# Sheet1.net
KiCad netlist of a schematic drawn in Altium Designer
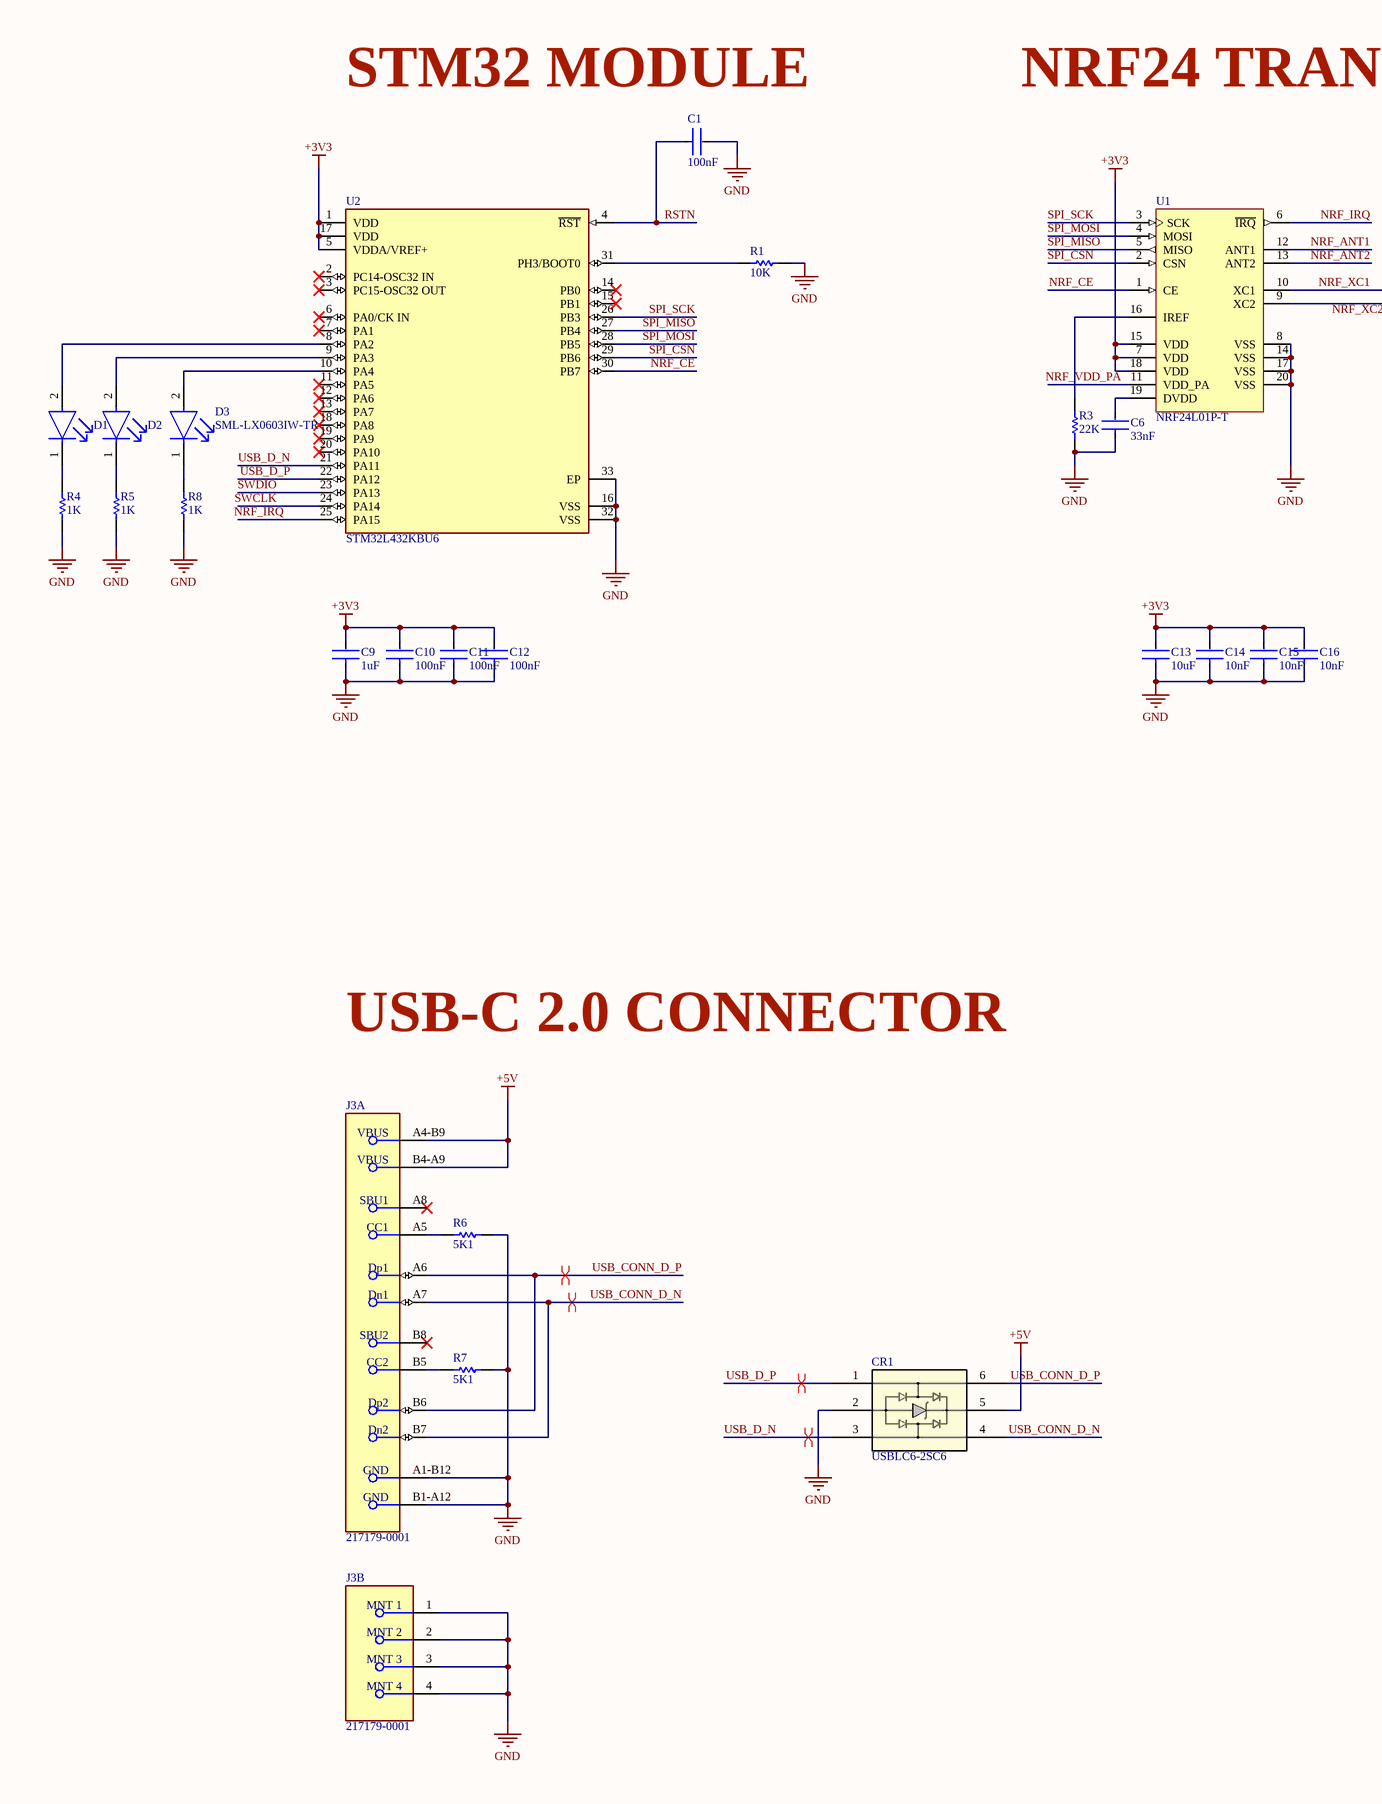
[diagram p0: Sheet1.SchDoc, left]
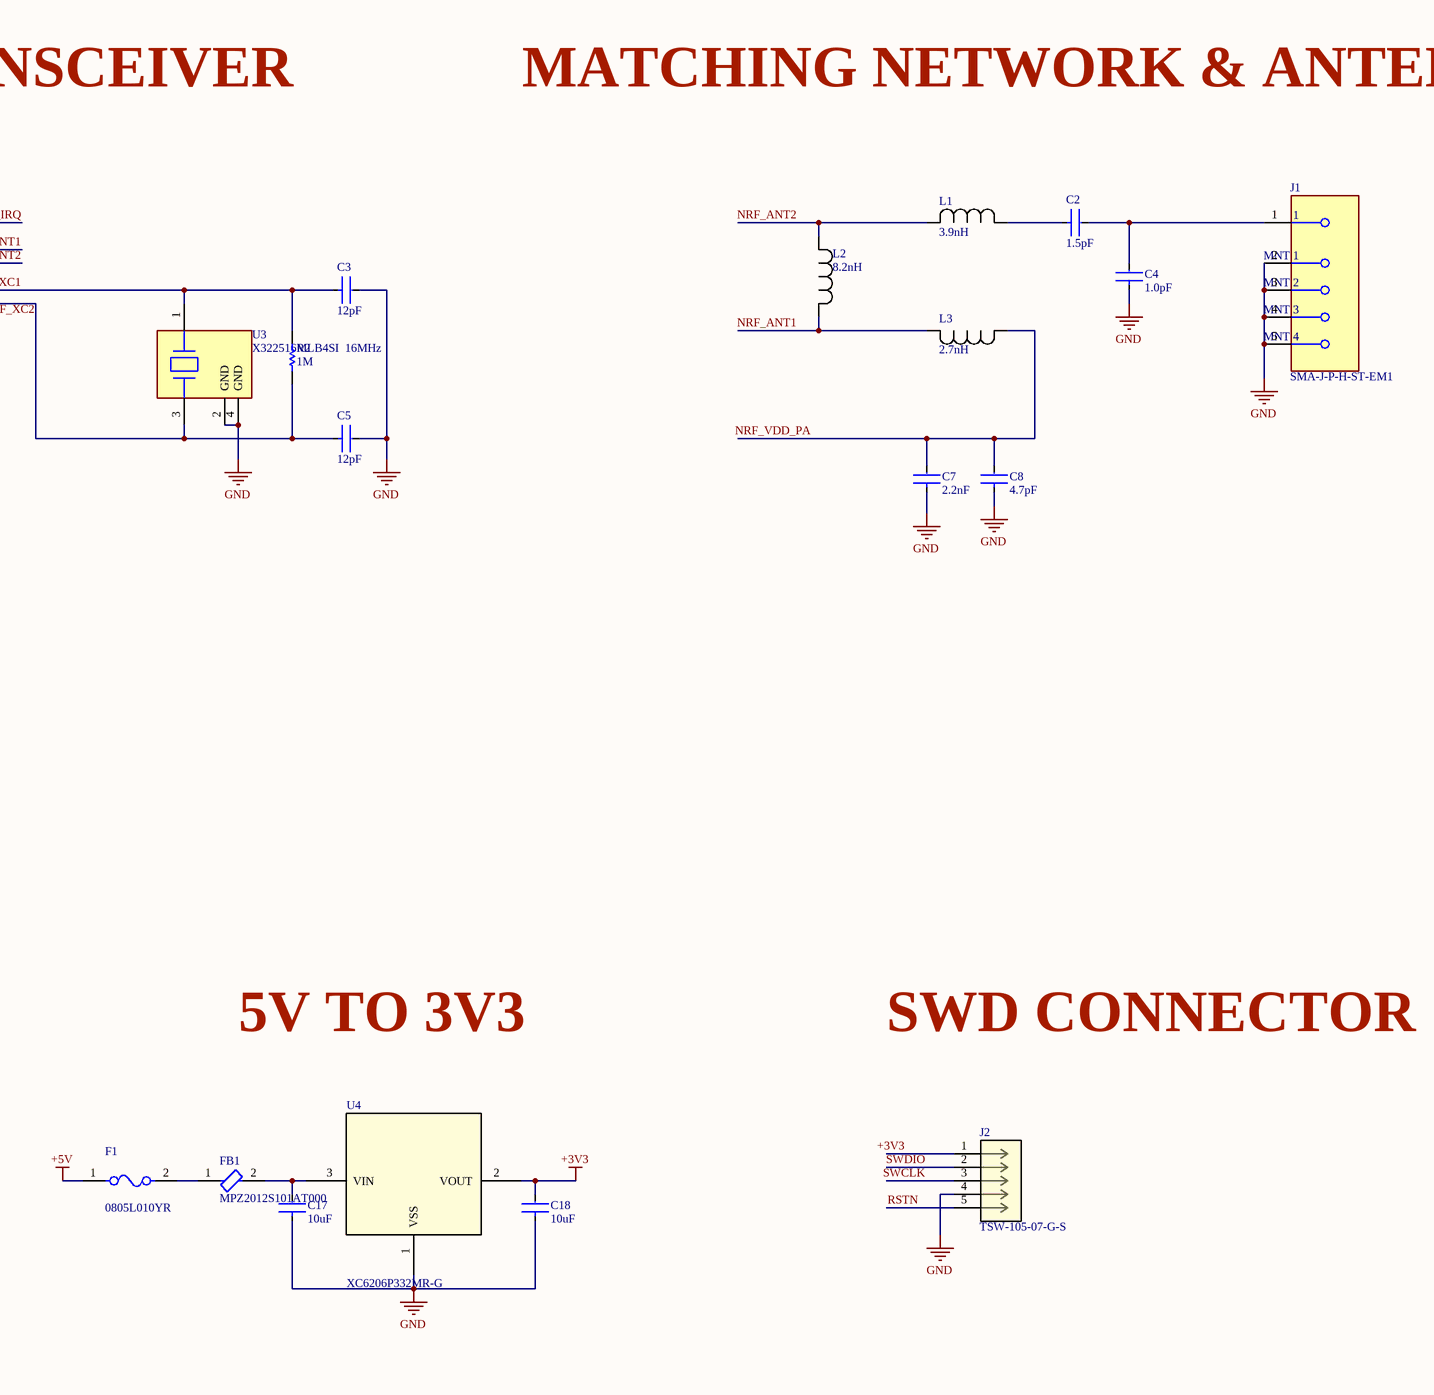
[diagram p1: Sheet1.SchDoc, right]

(export (version "E")
  (design (tool "Eeschema 10.0.6"))
  (components
    (comp (ref "C1")
      (value "100nF")
      (footprint "CAPC1005X55N")
      (description "Chip Capacitor, 100 nF")
      (fields (field (name "LCSC PART #") "C1525"))
      (libsource (lib "Schlib1") (part "CAP-0402-100NF"))
    )
    (comp (ref "C2")
      (value "1.5pF")
      (footprint "CAPC1005X55N")
      (description "Chip Capacitor, 1.5 pF")
      (fields (field (name "LCSC PART #") "C76901"))
      (libsource (lib "Schlib1") (part "CAP-0402-1P5F"))
    )
    (comp (ref "C3")
      (value "12pF")
      (footprint "CAPC1005X55N")
      (description "Chip Capacitor, 12 pF")
      (fields (field (name "LCSC PART #") "C2235030"))
      (libsource (lib "Schlib1") (part "CAP-0402-12PF"))
    )
    (comp (ref "C4")
      (value "1.0pF")
      (footprint "CAPC1005X55N")
      (description "Chip Capacitor, 1.0 pF")
      (fields (field (name "LCSC PART #") "C76898"))
      (libsource (lib "Schlib1") (part "CAP-0402-1PF"))
    )
    (comp (ref "C5")
      (value "12pF")
      (footprint "CAPC1005X55N")
      (description "Chip Capacitor, 12 pF")
      (fields (field (name "LCSC PART #") "C2235030"))
      (libsource (lib "Schlib1") (part "CAP-0402-12PF"))
    )
    (comp (ref "C6")
      (value "33nF")
      (footprint "CAPC1005X55N")
      (description "Chip Capacitor, 33 nF")
      (fields (field (name "LCSC PART #") "C126535"))
      (libsource (lib "Schlib1") (part "CAP-0402-33NF"))
    )
    (comp (ref "C7")
      (value "2.2nF")
      (footprint "CAPC1005X55N")
      (description "Chip Capacitor, 2.2 nF")
      (fields (field (name "LCSC PART #") "C2987940"))
      (libsource (lib "Schlib1") (part "CAP-0402-2N2F"))
    )
    (comp (ref "C8")
      (value "4.7pF")
      (footprint "CAPC1005X55N")
      (description "Chip Capacitor, 4.7 pF")
      (fields (field (name "LCSC PART #") "C161327"))
      (libsource (lib "Schlib1") (part "CAP-0402-4P7F"))
    )
    (comp (ref "C9")
      (value "1uF")
      (footprint "CAPC1005X55N")
      (description "Chip Capacitor, 1 uF")
      (fields (field (name "LCSC PART #") "C52923"))
      (libsource (lib "Schlib1") (part "CAP-0402-1UF"))
    )
    (comp (ref "C10")
      (value "100nF")
      (footprint "CAPC1005X55N")
      (description "Chip Capacitor, 100 nF")
      (fields (field (name "LCSC PART #") "C1525"))
      (libsource (lib "Schlib1") (part "CAP-0402-100NF"))
    )
    (comp (ref "C11")
      (value "100nF")
      (footprint "CAPC1005X55N")
      (description "Chip Capacitor, 100 nF")
      (fields (field (name "LCSC PART #") "C1525"))
      (libsource (lib "Schlib1") (part "CAP-0402-100NF"))
    )
    (comp (ref "C12")
      (value "100nF")
      (footprint "CAPC1005X55N")
      (description "Chip Capacitor, 100 nF")
      (fields (field (name "LCSC PART #") "C1525"))
      (libsource (lib "Schlib1") (part "CAP-0402-100NF"))
    )
    (comp (ref "C13")
      (value "10uF")
      (footprint "CAPC1608X90")
      (description "Chip Capacitor, 10 uF")
      (fields (field (name "LCSC PART #") "C22418930"))
      (libsource (lib "Schlib1") (part "CAP-0603-10UF"))
    )
    (comp (ref "C14")
      (value "10nF")
      (footprint "CAPC1005X55N")
      (description "Chip Capacitor, 10 nF")
      (fields (field (name "LCSC PART #") "C15195"))
      (libsource (lib "Schlib1") (part "CAP-0402-10NF"))
    )
    (comp (ref "C15")
      (value "10nF")
      (footprint "CAPC1005X55N")
      (description "Chip Capacitor, 10 nF")
      (fields (field (name "LCSC PART #") "C15195"))
      (libsource (lib "Schlib1") (part "CAP-0402-10NF"))
    )
    (comp (ref "C16")
      (value "10nF")
      (footprint "CAPC1005X55N")
      (description "Chip Capacitor, 10 nF")
      (fields (field (name "LCSC PART #") "C15195"))
      (libsource (lib "Schlib1") (part "CAP-0402-10NF"))
    )
    (comp (ref "C17")
      (value "10uF")
      (footprint "CAPC1608X90")
      (description "Chip Capacitor, 10 uF")
      (fields (field (name "LCSC PART #") "C22418930"))
      (libsource (lib "Schlib1") (part "CAP-0603-10UF"))
    )
    (comp (ref "C18")
      (value "10uF")
      (footprint "CAPC1608X90")
      (description "Chip Capacitor, 10 uF")
      (fields (field (name "LCSC PART #") "C22418930"))
      (libsource (lib "Schlib1") (part "CAP-0603-10UF"))
    )
    (comp (ref "CR1")
      (value "USBLC6-2SC6")
      (footprint "SOT23-6L_STM")
      (description "ESD Protection for USB 2.0 High Speed")
      (fields
        (field (name "LCSC PART #") "C5261088")
        (field (name "COPYRIGHT") "Copyright (C) 2025 Ultra Librarian. All rights reserved.")
      )
      (libsource (lib "Schlib1") (part "USBLC6-2SC6"))
    )
    (comp (ref "D1")
      (value "SML-LX0603IW-TR")
      (footprint "FP-SML-LX0603IW-TR-MFG")
      (description "LED RED DIFFUSED SMD")
      (fields (field (name "LCSC PART #") "C5354817"))
      (libsource (lib "Schlib1") (part "SML-LX0603IW-TR"))
    )
    (comp (ref "D2")
      (value "SML-LX0603IW-TR")
      (footprint "FP-SML-LX0603IW-TR-MFG")
      (description "LED RED DIFFUSED SMD")
      (fields (field (name "LCSC PART #") "C5354817"))
      (libsource (lib "Schlib1") (part "SML-LX0603IW-TR"))
    )
    (comp (ref "D3")
      (value "SML-LX0603IW-TR")
      (footprint "FP-SML-LX0603IW-TR-MFG")
      (description "LED RED DIFFUSED SMD")
      (fields (field (name "LCSC PART #") "C5354817"))
      (libsource (lib "Schlib1") (part "SML-LX0603IW-TR"))
    )
    (comp (ref "F1")
      (value "0805L010YR")
      (footprint "FP-0805L010-MFG")
      (fields (field (name "LCSC PART #") "C207020"))
      (libsource (lib "Schlib1") (part "0805L010YR"))
    )
    (comp (ref "FB1")
      (value "MPZ2012S101AT000")
      (footprint "FP-MPZ2012-IPC_A")
      (description "FERRITE BEAD 100 OHM 0805 1LN")
      (fields (field (name "TOLERANCE") "25%") (field (name "LCSC PART #") "C15957"))
      (libsource (lib "Schlib1") (part "MPZ2012S101AT000"))
    )
    (comp (ref "J1")
      (value "SMA-J-P-H-ST-EM1")
      (footprint "FP-SMA-J-P-H-ST-EM1-MFG")
      (description "CONN SMA JACK STR 50OHM EDGE MNT")
      (fields (field (name "LCSC PART #") "C5199907"))
      (libsource (lib "Schlib1") (part "SMA-J-P-H-ST-EM1"))
    )
    (comp (ref "J2")
      (value "TSW-105-07-G-S")
      (footprint "CON5_1X5_TU_TSW")
      (description "Conn Unshrouded Header HDR 5 POS 2.54mm Solder ST Top Entry Thru-Hole Bag")
      (fields
        (field (name "LCSC PART #") "C5993812")
        (field (name "COPYRIGHT") "Copyright (C) 2025 Ultra Librarian. All rights reserved.")
      )
      (libsource (lib "Schlib1") (part "TSW-105-07-G-S"))
    )
    (comp (ref "J3")
      (value "217179-0001")
      (footprint "FP-2171790001-MFG")
      (description "CONN RCP USB2.0 TYP C 24P SMD RA")
      (fields (field (name "LCSC PART #") "C3197684"))
      (libsource (lib "Schlib1") (part "217179-0001"))
    )
    (comp (ref "L1")
      (value "3.9nH")
      (footprint "IND_LQG15HS3N3S02D_MUR")
      (description "Inductor SMD")
      (fields
        (field (name "LCSC PART #") "C77109")
        (field (name "COPYRIGHT") "Copyright (C) 2026 Ultra Librarian. All rights reserved.")
      )
      (libsource (lib "Schlib1") (part "IND SMD 3.9nH"))
    )
    (comp (ref "L2")
      (value "8.2nH")
      (footprint "IND_LQG15HS3N3S02D_MUR")
      (description "Inductor SMD")
      (fields
        (field (name "LCSC PART #") "C98003")
        (field (name "COPYRIGHT") "Copyright (C) 2026 Ultra Librarian. All rights reserved.")
      )
      (libsource (lib "Schlib1") (part "IND SMD 8.2nH"))
    )
    (comp (ref "L3")
      (value "2.7nH")
      (footprint "IND_LQG15HS3N3S02D_MUR")
      (description "Inductor SMD")
      (fields
        (field (name "LCSC PART #") "C77108")
        (field (name "COPYRIGHT") "Copyright (C) 2026 Ultra Librarian. All rights reserved.")
      )
      (libsource (lib "Schlib1") (part "IND SMD 2.7nH"))
    )
    (comp (ref "R1")
      (value "10K")
      (footprint "RESC1005X37N")
      (description "RES 10kΩ ±1% 62.5mW 0402")
      (fields (field (name "LCSC PART #") "C60490"))
      (libsource (lib "Schlib1") (part "RES-0402-10K"))
    )
    (comp (ref "R2")
      (value "1M")
      (footprint "RESC1005X37N")
      (description "RES 1MΩ ±1% 62.5mW 0402")
      (fields (field (name "LCSC PART #") "C2906900"))
      (libsource (lib "Schlib1") (part "RES-0402-1M"))
    )
    (comp (ref "R3")
      (value "22K")
      (footprint "RESC1005X37N")
      (description "RES 22kΩ ±1% 62.5mW 0402")
      (fields (field (name "LCSC PART #") "C82868"))
      (libsource (lib "Schlib1") (part "RES-0402-22K"))
    )
    (comp (ref "R4")
      (value "1K")
      (footprint "RESC1608X55N")
      (description "RES 1KΩ ±1% 62.5mW 0603")
      (fields (field (name "LCSC PART #") "C2907002"))
      (libsource (lib "Schlib1") (part "RES-0603-1K"))
    )
    (comp (ref "R5")
      (value "1K")
      (footprint "RESC1608X55N")
      (description "RES 1KΩ ±1% 62.5mW 0603")
      (fields (field (name "LCSC PART #") "C2907002"))
      (libsource (lib "Schlib1") (part "RES-0603-1K"))
    )
    (comp (ref "R6")
      (value "5K1")
      (footprint "RESC1005X37N")
      (description "RES 5K1Ω ±1% 62.5mW 0402")
      (fields (field (name "LCSC PART #") "C723526"))
      (libsource (lib "Schlib1") (part "RES-0402-5K1"))
    )
    (comp (ref "R7")
      (value "5K1")
      (footprint "RESC1005X37N")
      (description "RES 5K1Ω ±1% 62.5mW 0402")
      (fields (field (name "LCSC PART #") "C723526"))
      (libsource (lib "Schlib1") (part "RES-0402-5K1"))
    )
    (comp (ref "R8")
      (value "1K")
      (footprint "RESC1608X55N")
      (description "RES 1KΩ ±1% 62.5mW 0603")
      (fields (field (name "LCSC PART #") "C2907002"))
      (libsource (lib "Schlib1") (part "RES-0603-1K"))
    )
    (comp (ref "U1")
      (value "NRF24L01P-T")
      (footprint "NRSC-QFN-20_L")
      (description "Single Chip Transceiver, 2.4 GHz, 60 mW, 1.9 to 3.6 V, -40 to 85 degC, 20-Pin QFN, RoHS, Tray")
      (fields (field (name "MANUFACTURER") "Nordic Semiconductor") (field (name "LCSC PART #") "C1526140"))
      (libsource (lib "Schlib1") (part "NRF24L01P-T"))
    )
    (comp (ref "U2")
      (value "STM32L432KBU6")
      (footprint "FP-UFQFPN32-A0B8-MFG")
      (description "IC MCU 32BIT 128KB FLASH 32QFPN")
      (fields
        (field (name "MANUFACTURER") "STMicroelectronics")
        (field (name "OCTOPART") "https://octopart.com/stm32l432kbu6-stmicroelectronics-74568735")
      )
      (libsource (lib "Schlib1") (part "STM32L432KBU6"))
    )
    (comp (ref "U3")
      (value "X322516MLB4SI  16MHz")
      (footprint "CHIP_X32B4SI_SYX")
      (description "CRYSTAL 16MHz 9pF SMD")
      (fields
        (field (name "MANUFACTURER_PART_NUMBER") "X322516MLB4SI")
        (field (name "LCSC PART #") "C13738")
        (field (name "COPYRIGHT") "Copyright (C) 2025 Ultra Librarian. All rights reserved.")
      )
      (libsource (lib "Schlib1") (part "X322516MLB4SI"))
    )
    (comp (ref "U4")
      (value "XC6206P332MR-G")
      (footprint "SOT-23_TOR")
      (description "Low ESR Cap. Compatible Positive Voltage Regulators")
      (fields
        (field (name "LCSC PART #") "C5446")
        (field (name "COPYRIGHT") "Copyright (C) 2026 Ultra Librarian. All rights reserved.")
      )
      (libsource (lib "Schlib1") (part "XC6206P332MR-G"))
    )
  )
  (nets
    (net (code "1") (name "+3V3") (class "Default")
      (node (ref "C10") (pin "2") (pinfunction "2_2") (pintype "passive"))
      (node (ref "C11") (pin "2") (pinfunction "2_2") (pintype "passive"))
      (node (ref "C12") (pin "2") (pinfunction "2_2") (pintype "passive"))
      (node (ref "C13") (pin "2") (pinfunction "2_2") (pintype "passive"))
      (node (ref "C14") (pin "2") (pinfunction "2_2") (pintype "passive"))
      (node (ref "C15") (pin "2") (pinfunction "2_2") (pintype "passive"))
      (node (ref "C16") (pin "2") (pinfunction "2_2") (pintype "passive"))
      (node (ref "C18") (pin "2") (pinfunction "2_2") (pintype "passive"))
      (node (ref "C9") (pin "2") (pinfunction "2_2") (pintype "passive"))
      (node (ref "J2") (pin "1") (pinfunction "1_1") (pintype "passive"))
      (node (ref "U1") (pin "15") (pinfunction "VDD_15") (pintype "power_in"))
      (node (ref "U1") (pin "18") (pinfunction "VDD_18") (pintype "power_in"))
      (node (ref "U1") (pin "7") (pinfunction "VDD_7") (pintype "power_in"))
      (node (ref "U2") (pin "1") (pinfunction "VDD_1") (pintype "power_in"))
      (node (ref "U2") (pin "17") (pinfunction "VDD_17") (pintype "power_in"))
      (node (ref "U2") (pin "5") (pinfunction "VDDA/VREF+_5") (pintype "power_in"))
      (node (ref "U4") (pin "2") (pinfunction "VOUT_2") (pintype "power_in"))
    )
    (net (code "2") (name "+5V") (class "Default")
      (node (ref "CR1") (pin "5") (pinfunction "5_5") (pintype "passive"))
      (node (ref "F1") (pin "1") (pinfunction "1_1") (pintype "passive"))
      (node (ref "J3") (pin "A4-B9") (pinfunction "VBUS_A4-B9") (pintype "power_in"))
      (node (ref "J3") (pin "B4-A9") (pinfunction "VBUS_B4-A9") (pintype "power_in"))
    )
    (net (code "3") (name "/NRF_ANT1") (class "Default")
      (node (ref "L2") (pin "1") (pinfunction "1_1") (pintype "passive"))
      (node (ref "L3") (pin "2") (pinfunction "2_2") (pintype "passive"))
      (node (ref "U1") (pin "12") (pinfunction "ANT1_12") (pintype "passive"))
    )
    (net (code "4") (name "/NRF_ANT2") (class "Default")
      (node (ref "L1") (pin "2") (pinfunction "2_2") (pintype "passive"))
      (node (ref "L2") (pin "2") (pinfunction "2_2") (pintype "passive"))
      (node (ref "U1") (pin "13") (pinfunction "ANT2_13") (pintype "passive"))
    )
    (net (code "5") (name "/NRF_CE") (class "Default")
      (node (ref "U1") (pin "1") (pinfunction "CE_1") (pintype "input"))
      (node (ref "U2") (pin "30") (pinfunction "PB7_30") (pintype "bidirectional"))
    )
    (net (code "6") (name "/NRF_IRQ") (class "Default")
      (node (ref "U1") (pin "6") (pinfunction "~{IRQ}_6") (pintype "output"))
      (node (ref "U2") (pin "25") (pinfunction "PA15_25") (pintype "bidirectional"))
    )
    (net (code "7") (name "/NRF_VDD_PA") (class "Default")
      (node (ref "C7") (pin "2") (pinfunction "2_2") (pintype "passive"))
      (node (ref "C8") (pin "2") (pinfunction "2_2") (pintype "passive"))
      (node (ref "L3") (pin "1") (pinfunction "1_1") (pintype "passive"))
      (node (ref "U1") (pin "11") (pinfunction "VDD_PA_11") (pintype "power_in"))
    )
    (net (code "8") (name "/NRF_XC1") (class "Default")
      (node (ref "C3") (pin "1") (pinfunction "1_1") (pintype "passive"))
      (node (ref "R2") (pin "2") (pinfunction "2_2") (pintype "passive"))
      (node (ref "U1") (pin "10") (pinfunction "XC1_10") (pintype "passive"))
      (node (ref "U3") (pin "1") (pinfunction "1_1") (pintype "passive"))
    )
    (net (code "9") (name "/NRF_XC2") (class "Default")
      (node (ref "C5") (pin "1") (pinfunction "1_1") (pintype "passive"))
      (node (ref "R2") (pin "1") (pinfunction "1_1") (pintype "passive"))
      (node (ref "U1") (pin "9") (pinfunction "XC2_9") (pintype "passive"))
      (node (ref "U3") (pin "3") (pinfunction "3_3") (pintype "passive"))
    )
    (net (code "10") (name "/RSTN") (class "Default")
      (node (ref "C1") (pin "1") (pinfunction "1_1") (pintype "passive"))
      (node (ref "J2") (pin "5") (pinfunction "5_5") (pintype "passive"))
      (node (ref "U2") (pin "4") (pinfunction "~{RST}_4") (pintype "input"))
    )
    (net (code "11") (name "/SPI_CSN") (class "Default")
      (node (ref "U1") (pin "2") (pinfunction "CSN_2") (pintype "input"))
      (node (ref "U2") (pin "29") (pinfunction "PB6_29") (pintype "bidirectional"))
    )
    (net (code "12") (name "/SPI_MISO") (class "Default")
      (node (ref "U1") (pin "5") (pinfunction "MISO_5") (pintype "output"))
      (node (ref "U2") (pin "27") (pinfunction "PB4_27") (pintype "bidirectional"))
    )
    (net (code "13") (name "/SPI_MOSI") (class "Default")
      (node (ref "U1") (pin "4") (pinfunction "MOSI_4") (pintype "input"))
      (node (ref "U2") (pin "28") (pinfunction "PB5_28") (pintype "bidirectional"))
    )
    (net (code "14") (name "/SPI_SCK") (class "Default")
      (node (ref "U1") (pin "3") (pinfunction "SCK_3") (pintype "input"))
      (node (ref "U2") (pin "26") (pinfunction "PB3_26") (pintype "bidirectional"))
    )
    (net (code "15") (name "/SWCLK") (class "Default")
      (node (ref "J2") (pin "3") (pinfunction "3_3") (pintype "passive"))
      (node (ref "U2") (pin "24") (pinfunction "PA14_24") (pintype "bidirectional"))
    )
    (net (code "16") (name "/SWDIO") (class "Default")
      (node (ref "J2") (pin "2") (pinfunction "2_2") (pintype "passive"))
      (node (ref "U2") (pin "23") (pinfunction "PA13_23") (pintype "bidirectional"))
    )
    (net (code "17") (name "/USB_CONN_D_N") (class "Default")
      (node (ref "CR1") (pin "4") (pinfunction "4_4") (pintype "passive"))
      (node (ref "J3") (pin "A7") (pinfunction "Dn1_A7") (pintype "bidirectional"))
      (node (ref "J3") (pin "B7") (pinfunction "Dn2_B7") (pintype "bidirectional"))
    )
    (net (code "18") (name "/USB_CONN_D_P") (class "Default")
      (node (ref "CR1") (pin "6") (pinfunction "6_6") (pintype "passive"))
      (node (ref "J3") (pin "A6") (pinfunction "Dp1_A6") (pintype "bidirectional"))
      (node (ref "J3") (pin "B6") (pinfunction "Dp2_B6") (pintype "bidirectional"))
    )
    (net (code "19") (name "/USB_D_N") (class "Default")
      (node (ref "CR1") (pin "3") (pinfunction "3_3") (pintype "passive"))
      (node (ref "U2") (pin "21") (pinfunction "PA11_21") (pintype "bidirectional"))
    )
    (net (code "20") (name "/USB_D_P") (class "Default")
      (node (ref "CR1") (pin "1") (pinfunction "1_1") (pintype "passive"))
      (node (ref "U2") (pin "22") (pinfunction "PA12_22") (pintype "bidirectional"))
    )
    (net (code "21") (name "GND") (class "Default")
      (node (ref "C1") (pin "2") (pinfunction "2_2") (pintype "passive"))
      (node (ref "C10") (pin "1") (pinfunction "1_1") (pintype "passive"))
      (node (ref "C11") (pin "1") (pinfunction "1_1") (pintype "passive"))
      (node (ref "C12") (pin "1") (pinfunction "1_1") (pintype "passive"))
      (node (ref "C13") (pin "1") (pinfunction "1_1") (pintype "passive"))
      (node (ref "C14") (pin "1") (pinfunction "1_1") (pintype "passive"))
      (node (ref "C15") (pin "1") (pinfunction "1_1") (pintype "passive"))
      (node (ref "C16") (pin "1") (pinfunction "1_1") (pintype "passive"))
      (node (ref "C17") (pin "1") (pinfunction "1_1") (pintype "passive"))
      (node (ref "C18") (pin "1") (pinfunction "1_1") (pintype "passive"))
      (node (ref "C3") (pin "2") (pinfunction "2_2") (pintype "passive"))
      (node (ref "C4") (pin "1") (pinfunction "1_1") (pintype "passive"))
      (node (ref "C5") (pin "2") (pinfunction "2_2") (pintype "passive"))
      (node (ref "C6") (pin "1") (pinfunction "1_1") (pintype "passive"))
      (node (ref "C7") (pin "1") (pinfunction "1_1") (pintype "passive"))
      (node (ref "C8") (pin "1") (pinfunction "1_1") (pintype "passive"))
      (node (ref "C9") (pin "1") (pinfunction "1_1") (pintype "passive"))
      (node (ref "CR1") (pin "2") (pinfunction "2_2") (pintype "passive"))
      (node (ref "J1") (pin "2") (pinfunction "MNT_1_2") (pintype "passive"))
      (node (ref "J1") (pin "3") (pinfunction "MNT_2_3") (pintype "passive"))
      (node (ref "J1") (pin "4") (pinfunction "MNT_3_4") (pintype "passive"))
      (node (ref "J1") (pin "5") (pinfunction "MNT_4_5") (pintype "passive"))
      (node (ref "J2") (pin "4") (pinfunction "4_4") (pintype "passive"))
      (node (ref "J3") (pin "1") (pinfunction "MNT_1_1") (pintype "passive"))
      (node (ref "J3") (pin "2") (pinfunction "MNT_2_2") (pintype "passive"))
      (node (ref "J3") (pin "3") (pinfunction "MNT_3_3") (pintype "power_in"))
      (node (ref "J3") (pin "4") (pinfunction "MNT_4_4") (pintype "power_in"))
      (node (ref "J3") (pin "A1-B12") (pinfunction "GND_A1-B12") (pintype "power_in"))
      (node (ref "J3") (pin "B1-A12") (pinfunction "GND_B1-A12") (pintype "power_in"))
      (node (ref "R1") (pin "2") (pinfunction "2_2") (pintype "passive"))
      (node (ref "R3") (pin "1") (pinfunction "1_1") (pintype "passive"))
      (node (ref "R4") (pin "1") (pinfunction "1_1") (pintype "passive"))
      (node (ref "R5") (pin "1") (pinfunction "1_1") (pintype "passive"))
      (node (ref "R6") (pin "2") (pinfunction "2_2") (pintype "passive"))
      (node (ref "R7") (pin "2") (pinfunction "2_2") (pintype "passive"))
      (node (ref "R8") (pin "1") (pinfunction "1_1") (pintype "passive"))
      (node (ref "U1") (pin "14") (pinfunction "VSS_14") (pintype "power_in"))
      (node (ref "U1") (pin "17") (pinfunction "VSS_17") (pintype "power_in"))
      (node (ref "U1") (pin "20") (pinfunction "VSS_20") (pintype "power_in"))
      (node (ref "U1") (pin "8") (pinfunction "VSS_8") (pintype "power_in"))
      (node (ref "U2") (pin "16") (pinfunction "VSS_16") (pintype "power_in"))
      (node (ref "U2") (pin "32") (pinfunction "VSS_32") (pintype "power_in"))
      (node (ref "U2") (pin "33") (pinfunction "EP_33") (pintype "power_in"))
      (node (ref "U3") (pin "2") (pinfunction "GND_2") (pintype "power_in"))
      (node (ref "U3") (pin "4") (pinfunction "GND_4") (pintype "power_in"))
      (node (ref "U4") (pin "1") (pinfunction "VSS_1") (pintype "power_in"))
    )
    (net (code "22") (name "Net-(C2-Pad1)") (class "Default")
      (node (ref "C2") (pin "1") (pinfunction "1_1") (pintype "passive"))
      (node (ref "L1") (pin "1") (pinfunction "1_1") (pintype "passive"))
    )
    (net (code "23") (name "Net-(C2-Pad2)") (class "Default")
      (node (ref "C2") (pin "2") (pinfunction "2_2") (pintype "passive"))
      (node (ref "C4") (pin "2") (pinfunction "2_2") (pintype "passive"))
      (node (ref "J1") (pin "1") (pinfunction "1_1") (pintype "passive"))
    )
    (net (code "24") (name "Net-(D1-A)") (class "Default")
      (node (ref "D1") (pin "2") (pinfunction "A_2") (pintype "passive"))
      (node (ref "U2") (pin "8") (pinfunction "PA2_8") (pintype "bidirectional"))
    )
    (net (code "25") (name "Net-(D1-C)") (class "Default")
      (node (ref "D1") (pin "1") (pinfunction "C_1") (pintype "passive"))
      (node (ref "R4") (pin "2") (pinfunction "2_2") (pintype "passive"))
    )
    (net (code "26") (name "Net-(D2-A)") (class "Default")
      (node (ref "D2") (pin "2") (pinfunction "A_2") (pintype "passive"))
      (node (ref "U2") (pin "9") (pinfunction "PA3_9") (pintype "bidirectional"))
    )
    (net (code "27") (name "Net-(D2-C)") (class "Default")
      (node (ref "D2") (pin "1") (pinfunction "C_1") (pintype "passive"))
      (node (ref "R5") (pin "2") (pinfunction "2_2") (pintype "passive"))
    )
    (net (code "28") (name "Net-(D3-A)") (class "Default")
      (node (ref "D3") (pin "2") (pinfunction "A_2") (pintype "passive"))
      (node (ref "U2") (pin "10") (pinfunction "PA4_10") (pintype "bidirectional"))
    )
    (net (code "29") (name "Net-(D3-C)") (class "Default")
      (node (ref "D3") (pin "1") (pinfunction "C_1") (pintype "passive"))
      (node (ref "R8") (pin "2") (pinfunction "2_2") (pintype "passive"))
    )
    (net (code "30") (name "Net-(F1-Pad2)") (class "Default")
      (node (ref "F1") (pin "2") (pinfunction "2_2") (pintype "passive"))
      (node (ref "FB1") (pin "1") (pinfunction "1_1") (pintype "passive"))
    )
    (net (code "31") (name "Net-(J3A-CC1)") (class "Default")
      (node (ref "J3") (pin "A5") (pinfunction "CC1_A5") (pintype "passive"))
      (node (ref "R6") (pin "1") (pinfunction "1_1") (pintype "passive"))
    )
    (net (code "32") (name "Net-(J3A-CC2)") (class "Default")
      (node (ref "J3") (pin "B5") (pinfunction "CC2_B5") (pintype "passive"))
      (node (ref "R7") (pin "1") (pinfunction "1_1") (pintype "passive"))
    )
    (net (code "33") (name "Net-(U1-DVDD)") (class "Default")
      (node (ref "C6") (pin "2") (pinfunction "2_2") (pintype "passive"))
      (node (ref "U1") (pin "19") (pinfunction "DVDD_19") (pintype "power_in"))
    )
    (net (code "34") (name "Net-(U1-IREF)") (class "Default")
      (node (ref "R3") (pin "2") (pinfunction "2_2") (pintype "passive"))
      (node (ref "U1") (pin "16") (pinfunction "IREF_16") (pintype "passive"))
    )
    (net (code "35") (name "Net-(U2-PH3{slash}BOOT0)") (class "Default")
      (node (ref "R1") (pin "1") (pinfunction "1_1") (pintype "passive"))
      (node (ref "U2") (pin "31") (pinfunction "PH3/BOOT0_31") (pintype "bidirectional"))
    )
    (net (code "36") (name "Net-(U4-VIN)") (class "Default")
      (node (ref "C17") (pin "2") (pinfunction "2_2") (pintype "passive"))
      (node (ref "FB1") (pin "2") (pinfunction "2_2") (pintype "passive"))
      (node (ref "U4") (pin "3") (pinfunction "VIN_3") (pintype "power_in"))
    )
    (net (code "37") (name "unconnected-(J3A-SBU1-PadA8)") (class "Default")
      (node (ref "J3") (pin "A8") (pinfunction "SBU1_A8") (pintype "passive+no_connect"))
    )
    (net (code "38") (name "unconnected-(J3A-SBU2-PadB8)") (class "Default")
      (node (ref "J3") (pin "B8") (pinfunction "SBU2_B8") (pintype "passive+no_connect"))
    )
    (net (code "39") (name "unconnected-(U2-PA0{slash}CK_IN-Pad6)") (class "Default")
      (node (ref "U2") (pin "6") (pinfunction "PA0/CK_IN_6") (pintype "bidirectional+no_connect"))
    )
    (net (code "40") (name "unconnected-(U2-PA1-Pad7)") (class "Default")
      (node (ref "U2") (pin "7") (pinfunction "PA1_7") (pintype "bidirectional+no_connect"))
    )
    (net (code "41") (name "unconnected-(U2-PA5-Pad11)") (class "Default")
      (node (ref "U2") (pin "11") (pinfunction "PA5_11") (pintype "bidirectional+no_connect"))
    )
    (net (code "42") (name "unconnected-(U2-PA6-Pad12)") (class "Default")
      (node (ref "U2") (pin "12") (pinfunction "PA6_12") (pintype "bidirectional+no_connect"))
    )
    (net (code "43") (name "unconnected-(U2-PA7-Pad13)") (class "Default")
      (node (ref "U2") (pin "13") (pinfunction "PA7_13") (pintype "bidirectional+no_connect"))
    )
    (net (code "44") (name "unconnected-(U2-PA8-Pad18)") (class "Default")
      (node (ref "U2") (pin "18") (pinfunction "PA8_18") (pintype "bidirectional+no_connect"))
    )
    (net (code "45") (name "unconnected-(U2-PA9-Pad19)") (class "Default")
      (node (ref "U2") (pin "19") (pinfunction "PA9_19") (pintype "bidirectional+no_connect"))
    )
    (net (code "46") (name "unconnected-(U2-PA10-Pad20)") (class "Default")
      (node (ref "U2") (pin "20") (pinfunction "PA10_20") (pintype "bidirectional+no_connect"))
    )
    (net (code "47") (name "unconnected-(U2-PB0-Pad14)") (class "Default")
      (node (ref "U2") (pin "14") (pinfunction "PB0_14") (pintype "bidirectional+no_connect"))
    )
    (net (code "48") (name "unconnected-(U2-PB1-Pad15)") (class "Default")
      (node (ref "U2") (pin "15") (pinfunction "PB1_15") (pintype "bidirectional+no_connect"))
    )
    (net (code "49") (name "unconnected-(U2-PC14-OSC32_IN-Pad2)") (class "Default")
      (node (ref "U2") (pin "2") (pinfunction "PC14-OSC32_IN_2") (pintype "bidirectional+no_connect"))
    )
    (net (code "50") (name "unconnected-(U2-PC15-OSC32_OUT-Pad3)") (class "Default")
      (node (ref "U2") (pin "3") (pinfunction "PC15-OSC32_OUT_3") (pintype "bidirectional+no_connect"))
    )
  )
)
